# SCH_UWB_AiThinker_BU01_2023-06-05.net
KiCad netlist of a schematic drawn in EasyEDA
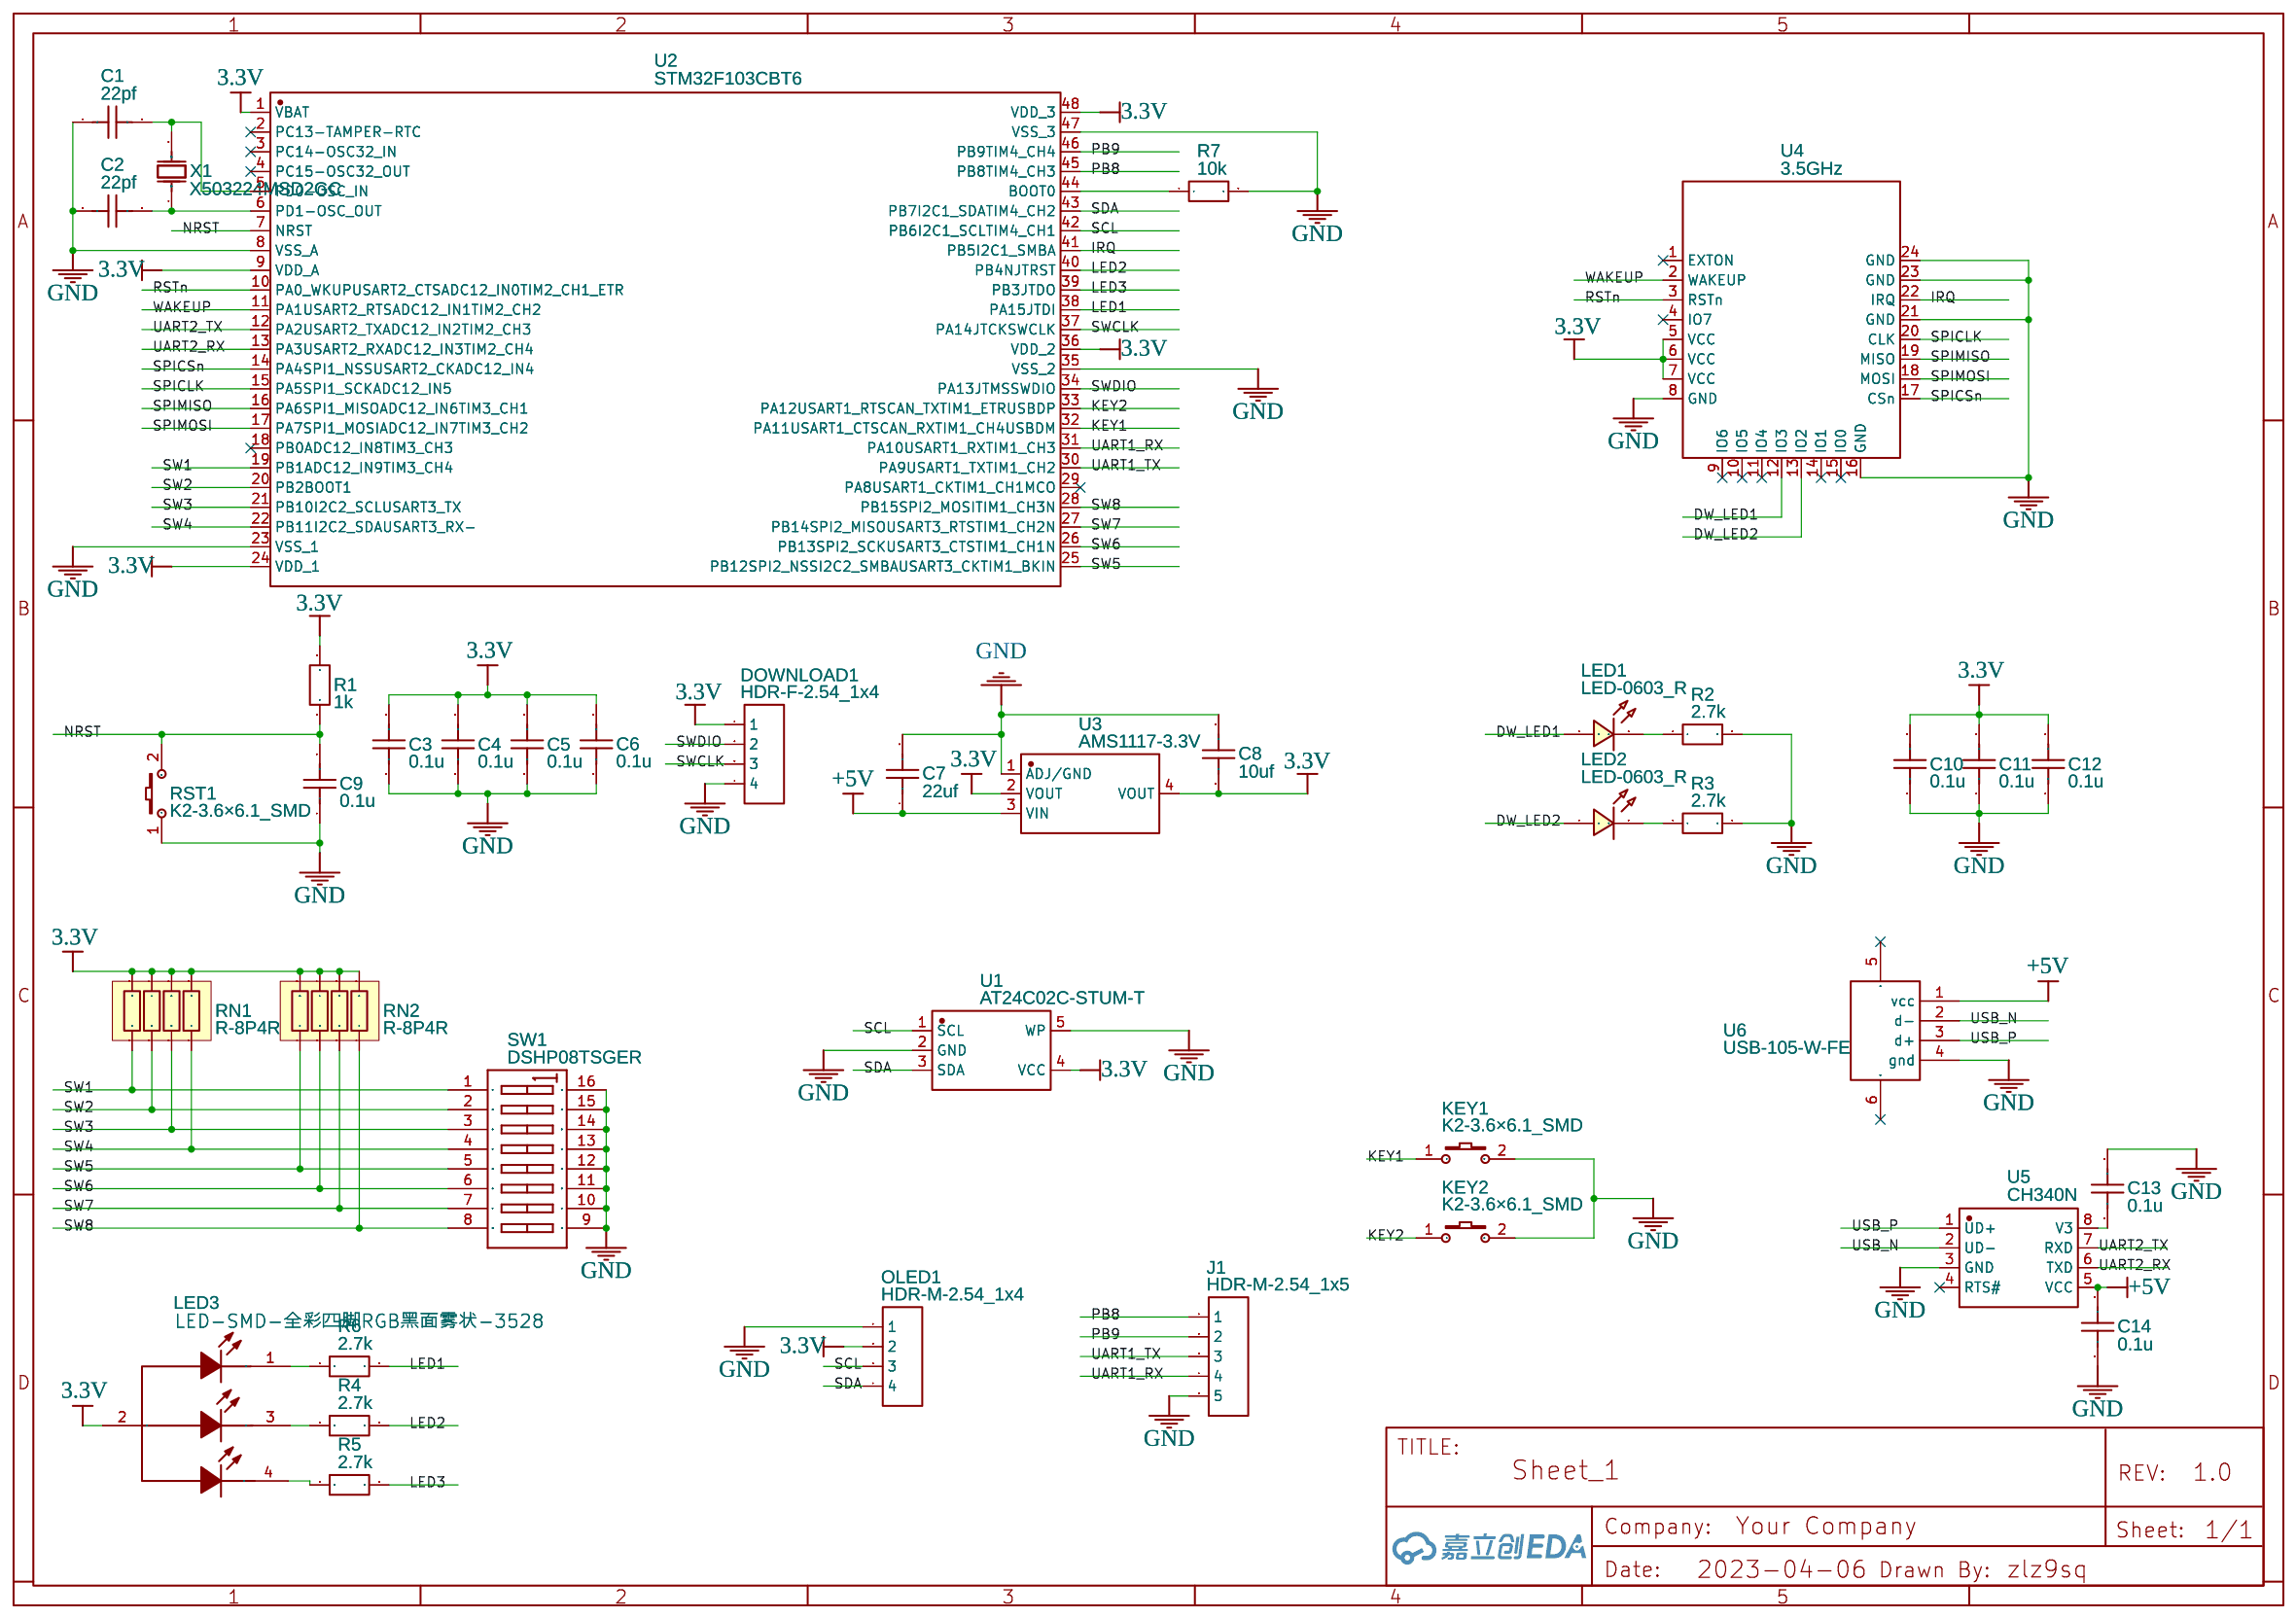
[diagram p0: schematic sheet]

(export (version "E")
  (design (tool "Eeschema 10.0.6"))
  (components
    (comp (ref "C1") (value "22pf") (libsource (lib "") (part "C_0603_US_1")))
    (comp (ref "C2") (value "22pf") (libsource (lib "") (part "C_0603_US_1")))
    (comp (ref "C3") (value "0.1u") (libsource (lib "") (part "C_0603_US")))
    (comp (ref "C4") (value "0.1u") (libsource (lib "") (part "C_0603_US")))
    (comp (ref "C5") (value "0.1u") (libsource (lib "") (part "C_0603_US")))
    (comp (ref "C6") (value "0.1u") (libsource (lib "") (part "C_0603_US")))
    (comp (ref "C7") (value "22uf") (libsource (lib "") (part "C_0805_US_1")))
    (comp (ref "C8") (value "10uf") (libsource (lib "") (part "C_0805_US")))
    (comp (ref "C9") (value "0.1u") (libsource (lib "") (part "C_0603_US")))
    (comp (ref "C10") (value "0.1u") (libsource (lib "") (part "C_0603_US")))
    (comp (ref "C11") (value "0.1u") (libsource (lib "") (part "C_0603_US")))
    (comp (ref "C12") (value "0.1u") (libsource (lib "") (part "C_0603_US")))
    (comp (ref "C13") (value "0.1u") (libsource (lib "") (part "C_0603_US")))
    (comp (ref "C14") (value "0.1u") (libsource (lib "") (part "C_0603_US")))
    (comp (ref "DOWNLOAD1")
      (value "HDR-F-2.54_1x4")
      (fields (field (name "BOM_Supplier Part") "C225501"))
      (libsource (lib "") (part "HDR-F-2.54_1x4"))
    )
    (comp (ref "J1")
      (value "HDR-M-2.54_1x5")
      (fields (field (name "BOM_Supplier Part") "C358687"))
      (libsource (lib "") (part "HDR-M-2.54_1x5"))
    )
    (comp (ref "KEY1")
      (value "K2-3.6×6.1_SMD")
      (fields
        (field (name "BOM_Manufacturer Part") "K2-1107ST-A4SW-06")
        (field (name "BOM_Supplier Part") "C118141")
      )
      (libsource (lib "") (part "K2-3.6×6.1_SMD"))
    )
    (comp (ref "KEY2")
      (value "K2-3.6×6.1_SMD")
      (fields
        (field (name "BOM_Manufacturer Part") "K2-1107ST-A4SW-06")
        (field (name "BOM_Supplier Part") "C118141")
      )
      (libsource (lib "") (part "K2-3.6×6.1_SMD"))
    )
    (comp (ref "LED1")
      (value "LED-0603_R")
      (fields
        (field (name "BOM_Manufacturer Part") "19-217/R6C-AL1M2VY/3T")
        (field (name "BOM_Supplier Part") "C72044")
      )
      (libsource (lib "") (part "LED-0603_R"))
    )
    (comp (ref "LED2")
      (value "LED-0603_R")
      (fields
        (field (name "BOM_Manufacturer Part") "19-217/R6C-AL1M2VY/3T")
        (field (name "BOM_Supplier Part") "C72044")
      )
      (libsource (lib "") (part "LED-0603_R"))
    )
    (comp (ref "LED3")
      (value "LED-SMD-全彩四脚RGB黑面雾状-3528")
      (fields (field (name "BOM_Supplier Part") "C9900014091"))
      (libsource (lib "") (part "LED-SMD-全彩四脚RGB黑面雾状-3528"))
    )
    (comp (ref "OLED1")
      (value "HDR-M-2.54_1x4")
      (fields (field (name "BOM_Supplier Part") "C124378"))
      (libsource (lib "") (part "HDR-M-2.54_1x4"))
    )
    (comp (ref "R1") (value "1k") (libsource (lib "") (part "R_0603_EU")))
    (comp (ref "R2") (value "2.7k") (libsource (lib "") (part "R_0603_EU_1")))
    (comp (ref "R3") (value "2.7k") (libsource (lib "") (part "R_0603_EU_1")))
    (comp (ref "R4") (value "2.7k") (libsource (lib "") (part "R_0603_EU_1")))
    (comp (ref "R5") (value "2.7k") (libsource (lib "") (part "R_0603_EU_1")))
    (comp (ref "R6") (value "2.7k") (libsource (lib "") (part "R_0603_EU_1")))
    (comp (ref "R7") (value "10k") (libsource (lib "") (part "R_0603_EU_1")))
    (comp (ref "RN1") (value "R-8P4R") (libsource (lib "") (part "R-8P4R")))
    (comp (ref "RN2") (value "R-8P4R") (libsource (lib "") (part "R-8P4R")))
    (comp (ref "RST1")
      (value "K2-3.6×6.1_SMD")
      (fields
        (field (name "BOM_Manufacturer Part") "K2-1107ST-A4SW-06")
        (field (name "BOM_Supplier Part") "C118141")
      )
      (libsource (lib "") (part "K2-3.6×6.1_SMD_1"))
    )
    (comp (ref "SW1")
      (value "DSHP08TSGER")
      (fields (field (name "BOM_Supplier Part") "C40738"))
      (libsource (lib "") (part "DSHP08TSGER"))
    )
    (comp (ref "U1")
      (value "AT24C02C-STUM-T")
      (fields (field (name "BOM_Supplier Part") "C94534"))
      (libsource (lib "") (part "AT24C02C-STUM-T"))
    )
    (comp (ref "U2")
      (value "STM32F103CBT6")
      (fields (field (name "BOM_Supplier Part") "C8304"))
      (libsource (lib "") (part "STM32F103CBT6"))
    )
    (comp (ref "U3")
      (value "AMS1117-3.3V")
      (fields (field (name "BOM_Supplier Part") "C2688239"))
      (libsource (lib "") (part "AMS1117-3.3V"))
    )
    (comp (ref "U4")
      (value "3.5GHz")
      (fields (field (name "BOM_Manufacturer Part") "BU01") (field (name "BOM_Supplier Part") "C503604"))
      (libsource (lib "") (part "BU01"))
    )
    (comp (ref "U5")
      (value "CH340N")
      (fields (field (name "BOM_Supplier Part") "C506813"))
      (libsource (lib "") (part "CH340N"))
    )
    (comp (ref "U6")
      (value "USB-105-W-FE")
      (fields (field (name "BOM_Supplier Part") "C2939555"))
      (libsource (lib "") (part "USB-105-W-FE"))
    )
    (comp (ref "X1")
      (value "X503224MSD2GC")
      (fields (field (name "BOM_Supplier Part") "C48304"))
      (libsource (lib "") (part "X503224MSD2GC"))
    )
  )
  (nets
    (net (code "1") (name "+5V") (class "Default")
      (node (ref "C14") (pin "2") (pinfunction "2_2") (pintype "unspecified"))
      (node (ref "C7") (pin "1") (pinfunction "1_1") (pintype "unspecified"))
      (node (ref "U3") (pin "3") (pinfunction "VIN_3") (pintype "unspecified"))
      (node (ref "U5") (pin "5") (pinfunction "VCC_5") (pintype "unspecified"))
      (node (ref "U6") (pin "1") (pinfunction "vcc_1") (pintype "input"))
    )
    (net (code "2") (name "/DW_LED1") (class "Default")
      (node (ref "LED1") (pin "1") (pinfunction "1_1") (pintype "unspecified"))
      (node (ref "U4") (pin "12") (pinfunction "IO3_12") (pintype "unspecified"))
    )
    (net (code "3") (name "/DW_LED2") (class "Default")
      (node (ref "LED2") (pin "1") (pinfunction "1_1") (pintype "unspecified"))
      (node (ref "U4") (pin "13") (pinfunction "IO2_13") (pintype "unspecified"))
    )
    (net (code "4") (name "/IRQ") (class "Default")
      (node (ref "U2") (pin "41") (pinfunction "PB5I2C1_SMBA_41") (pintype "unspecified"))
      (node (ref "U4") (pin "22") (pinfunction "IRQ_22") (pintype "unspecified"))
    )
    (net (code "5") (name "/KEY1") (class "Default")
      (node (ref "KEY1") (pin "1") (pinfunction "1_1") (pintype "unspecified"))
      (node (ref "U2") (pin "32") (pinfunction "PA11USART1_CTSCAN_RXTIM1_CH4USBDM_32") (pintype "unspecified"))
    )
    (net (code "6") (name "/KEY2") (class "Default")
      (node (ref "KEY2") (pin "1") (pinfunction "1_1") (pintype "unspecified"))
      (node (ref "U2") (pin "33") (pinfunction "PA12USART1_RTSCAN_TXTIM1_ETRUSBDP_33") (pintype "unspecified"))
    )
    (net (code "7") (name "/LED1") (class "Default")
      (node (ref "R6") (pin "2") (pinfunction "2_2") (pintype "unspecified"))
      (node (ref "U2") (pin "38") (pinfunction "PA15JTDI_38") (pintype "unspecified"))
    )
    (net (code "8") (name "/LED2") (class "Default")
      (node (ref "R4") (pin "2") (pinfunction "2_2") (pintype "unspecified"))
      (node (ref "U2") (pin "40") (pinfunction "PB4NJTRST_40") (pintype "unspecified"))
    )
    (net (code "9") (name "/LED3") (class "Default")
      (node (ref "R5") (pin "2") (pinfunction "2_2") (pintype "unspecified"))
      (node (ref "U2") (pin "39") (pinfunction "PB3JTDO_39") (pintype "unspecified"))
    )
    (net (code "10") (name "/NRST") (class "Default")
      (node (ref "C9") (pin "2") (pinfunction "2_2") (pintype "unspecified"))
      (node (ref "R1") (pin "1") (pinfunction "1_1") (pintype "unspecified"))
      (node (ref "RST1") (pin "2") (pinfunction "2_2") (pintype "unspecified"))
      (node (ref "U2") (pin "7") (pinfunction "NRST_7") (pintype "unspecified"))
    )
    (net (code "11") (name "/PB8") (class "Default")
      (node (ref "J1") (pin "1") (pinfunction "1_1") (pintype "unspecified"))
      (node (ref "U2") (pin "45") (pinfunction "PB8TIM4_CH3_45") (pintype "unspecified"))
    )
    (net (code "12") (name "/PB9") (class "Default")
      (node (ref "J1") (pin "2") (pinfunction "2_2") (pintype "unspecified"))
      (node (ref "U2") (pin "46") (pinfunction "PB9TIM4_CH4_46") (pintype "unspecified"))
    )
    (net (code "13") (name "/RSTn") (class "Default")
      (node (ref "U2") (pin "10") (pinfunction "PA0_WKUPUSART2_CTSADC12_IN0TIM2_CH1_ETR_10") (pintype "unspecified"))
      (node (ref "U4") (pin "3") (pinfunction "RSTn_3") (pintype "unspecified"))
    )
    (net (code "14") (name "/SCL") (class "Default")
      (node (ref "OLED1") (pin "3") (pinfunction "3_3") (pintype "unspecified"))
      (node (ref "U1") (pin "1") (pinfunction "SCL_1") (pintype "unspecified"))
      (node (ref "U2") (pin "42") (pinfunction "PB6I2C1_SCLTIM4_CH1_42") (pintype "unspecified"))
    )
    (net (code "15") (name "/SDA") (class "Default")
      (node (ref "OLED1") (pin "4") (pinfunction "4_4") (pintype "unspecified"))
      (node (ref "U1") (pin "3") (pinfunction "SDA_3") (pintype "unspecified"))
      (node (ref "U2") (pin "43") (pinfunction "PB7I2C1_SDATIM4_CH2_43") (pintype "unspecified"))
    )
    (net (code "16") (name "/SPICLK") (class "Default")
      (node (ref "U2") (pin "15") (pinfunction "PA5SPI1_SCKADC12_IN5_15") (pintype "unspecified"))
      (node (ref "U4") (pin "20") (pinfunction "CLK_20") (pintype "unspecified"))
    )
    (net (code "17") (name "/SPICSn") (class "Default")
      (node (ref "U2") (pin "14") (pinfunction "PA4SPI1_NSSUSART2_CKADC12_IN4_14") (pintype "unspecified"))
      (node (ref "U4") (pin "17") (pinfunction "CSn_17") (pintype "unspecified"))
    )
    (net (code "18") (name "/SPIMISO") (class "Default")
      (node (ref "U2") (pin "16") (pinfunction "PA6SPI1_MISOADC12_IN6TIM3_CH1_16") (pintype "unspecified"))
      (node (ref "U4") (pin "19") (pinfunction "MISO_19") (pintype "unspecified"))
    )
    (net (code "19") (name "/SPIMOSI") (class "Default")
      (node (ref "U2") (pin "17") (pinfunction "PA7SPI1_MOSIADC12_IN7TIM3_CH2_17") (pintype "unspecified"))
      (node (ref "U4") (pin "18") (pinfunction "MOSI_18") (pintype "unspecified"))
    )
    (net (code "20") (name "/SW1") (class "Default")
      (node (ref "RN1") (pin "1") (pinfunction "1_1") (pintype "unspecified"))
      (node (ref "SW1") (pin "1") (pinfunction "A1_1") (pintype "unspecified"))
      (node (ref "U2") (pin "19") (pinfunction "PB1ADC12_IN9TIM3_CH4_19") (pintype "unspecified"))
    )
    (net (code "21") (name "/SW2") (class "Default")
      (node (ref "RN1") (pin "2") (pinfunction "2_2") (pintype "unspecified"))
      (node (ref "SW1") (pin "2") (pinfunction "A2_2") (pintype "unspecified"))
      (node (ref "U2") (pin "20") (pinfunction "PB2BOOT1_20") (pintype "unspecified"))
    )
    (net (code "22") (name "/SW3") (class "Default")
      (node (ref "RN1") (pin "3") (pinfunction "3_3") (pintype "unspecified"))
      (node (ref "SW1") (pin "3") (pinfunction "A3_3") (pintype "unspecified"))
      (node (ref "U2") (pin "21") (pinfunction "PB10I2C2_SCLUSART3_TX_21") (pintype "unspecified"))
    )
    (net (code "23") (name "/SW4") (class "Default")
      (node (ref "RN1") (pin "4") (pinfunction "4_4") (pintype "unspecified"))
      (node (ref "SW1") (pin "4") (pinfunction "A4_4") (pintype "unspecified"))
      (node (ref "U2") (pin "22") (pinfunction "PB11I2C2_SDAUSART3_RX-_22") (pintype "unspecified"))
    )
    (net (code "24") (name "/SW5") (class "Default")
      (node (ref "RN2") (pin "1") (pinfunction "1_1") (pintype "unspecified"))
      (node (ref "SW1") (pin "5") (pinfunction "A5_5") (pintype "unspecified"))
      (node (ref "U2") (pin "25") (pinfunction "PB12SPI2_NSSI2C2_SMBAUSART3_CKTIM1_BKIN_25") (pintype "unspecified"))
    )
    (net (code "25") (name "/SW6") (class "Default")
      (node (ref "RN2") (pin "2") (pinfunction "2_2") (pintype "unspecified"))
      (node (ref "SW1") (pin "6") (pinfunction "A6_6") (pintype "unspecified"))
      (node (ref "U2") (pin "26") (pinfunction "PB13SPI2_SCKUSART3_CTSTIM1_CH1N_26") (pintype "unspecified"))
    )
    (net (code "26") (name "/SW7") (class "Default")
      (node (ref "RN2") (pin "3") (pinfunction "3_3") (pintype "unspecified"))
      (node (ref "SW1") (pin "7") (pinfunction "A7_7") (pintype "unspecified"))
      (node (ref "U2") (pin "27") (pinfunction "PB14SPI2_MISOUSART3_RTSTIM1_CH2N_27") (pintype "unspecified"))
    )
    (net (code "27") (name "/SW8") (class "Default")
      (node (ref "RN2") (pin "4") (pinfunction "4_4") (pintype "unspecified"))
      (node (ref "SW1") (pin "8") (pinfunction "A8_8") (pintype "unspecified"))
      (node (ref "U2") (pin "28") (pinfunction "PB15SPI2_MOSITIM1_CH3N_28") (pintype "unspecified"))
    )
    (net (code "28") (name "/SWCLK") (class "Default")
      (node (ref "DOWNLOAD1") (pin "3") (pinfunction "3_3") (pintype "unspecified"))
      (node (ref "U2") (pin "37") (pinfunction "PA14JTCKSWCLK_37") (pintype "unspecified"))
    )
    (net (code "29") (name "/SWDIO") (class "Default")
      (node (ref "DOWNLOAD1") (pin "2") (pinfunction "2_2") (pintype "unspecified"))
      (node (ref "U2") (pin "34") (pinfunction "PA13JTMSSWDIO_34") (pintype "unspecified"))
    )
    (net (code "30") (name "/UART1_RX") (class "Default")
      (node (ref "J1") (pin "4") (pinfunction "4_4") (pintype "unspecified"))
      (node (ref "U2") (pin "31") (pinfunction "PA10USART1_RXTIM1_CH3_31") (pintype "unspecified"))
    )
    (net (code "31") (name "/UART1_TX") (class "Default")
      (node (ref "J1") (pin "3") (pinfunction "3_3") (pintype "unspecified"))
      (node (ref "U2") (pin "30") (pinfunction "PA9USART1_TXTIM1_CH2_30") (pintype "unspecified"))
    )
    (net (code "32") (name "/UART2_RX") (class "Default")
      (node (ref "U2") (pin "13") (pinfunction "PA3USART2_RXADC12_IN3TIM2_CH4_13") (pintype "unspecified"))
      (node (ref "U5") (pin "6") (pinfunction "TXD_6") (pintype "unspecified"))
    )
    (net (code "33") (name "/UART2_TX") (class "Default")
      (node (ref "U2") (pin "12") (pinfunction "PA2USART2_TXADC12_IN2TIM2_CH3_12") (pintype "unspecified"))
      (node (ref "U5") (pin "7") (pinfunction "RXD_7") (pintype "unspecified"))
    )
    (net (code "34") (name "/USB_N") (class "Default")
      (node (ref "U5") (pin "2") (pinfunction "UD-_2") (pintype "unspecified"))
      (node (ref "U6") (pin "2") (pinfunction "d-_2") (pintype "input"))
    )
    (net (code "35") (name "/USB_P") (class "Default")
      (node (ref "U5") (pin "1") (pinfunction "UD+_1") (pintype "unspecified"))
      (node (ref "U6") (pin "3") (pinfunction "d+_3") (pintype "input"))
    )
    (net (code "36") (name "/WAKEUP") (class "Default")
      (node (ref "U2") (pin "11") (pinfunction "PA1USART2_RTSADC12_IN1TIM2_CH2_11") (pintype "unspecified"))
      (node (ref "U4") (pin "2") (pinfunction "WAKEUP_2") (pintype "unspecified"))
    )
    (net (code "37") (name "3.3V") (class "Default")
      (node (ref "C10") (pin "2") (pinfunction "2_2") (pintype "unspecified"))
      (node (ref "C11") (pin "2") (pinfunction "2_2") (pintype "unspecified"))
      (node (ref "C12") (pin "2") (pinfunction "2_2") (pintype "unspecified"))
      (node (ref "C3") (pin "2") (pinfunction "2_2") (pintype "unspecified"))
      (node (ref "C4") (pin "2") (pinfunction "2_2") (pintype "unspecified"))
      (node (ref "C5") (pin "2") (pinfunction "2_2") (pintype "unspecified"))
      (node (ref "C6") (pin "2") (pinfunction "2_2") (pintype "unspecified"))
      (node (ref "C8") (pin "2") (pinfunction "2_2") (pintype "unspecified"))
      (node (ref "DOWNLOAD1") (pin "1") (pinfunction "1_1") (pintype "unspecified"))
      (node (ref "LED3") (pin "2") (pinfunction "2_2") (pintype "unspecified"))
      (node (ref "OLED1") (pin "2") (pinfunction "2_2") (pintype "unspecified"))
      (node (ref "R1") (pin "2") (pinfunction "2_2") (pintype "unspecified"))
      (node (ref "RN1") (pin "5") (pinfunction "5_5") (pintype "unspecified"))
      (node (ref "RN1") (pin "6") (pinfunction "6_6") (pintype "unspecified"))
      (node (ref "RN1") (pin "7") (pinfunction "7_7") (pintype "unspecified"))
      (node (ref "RN1") (pin "8") (pinfunction "8_8") (pintype "unspecified"))
      (node (ref "RN2") (pin "5") (pinfunction "5_5") (pintype "unspecified"))
      (node (ref "RN2") (pin "6") (pinfunction "6_6") (pintype "unspecified"))
      (node (ref "RN2") (pin "7") (pinfunction "7_7") (pintype "unspecified"))
      (node (ref "RN2") (pin "8") (pinfunction "8_8") (pintype "unspecified"))
      (node (ref "U1") (pin "4") (pinfunction "VCC_4") (pintype "unspecified"))
      (node (ref "U2") (pin "1") (pinfunction "VBAT_1") (pintype "unspecified"))
      (node (ref "U2") (pin "24") (pinfunction "VDD_1_24") (pintype "unspecified"))
      (node (ref "U2") (pin "36") (pinfunction "VDD_2_36") (pintype "unspecified"))
      (node (ref "U2") (pin "48") (pinfunction "VDD_3_48") (pintype "unspecified"))
      (node (ref "U2") (pin "9") (pinfunction "VDD_A_9") (pintype "unspecified"))
      (node (ref "U3") (pin "2") (pinfunction "VOUT_2") (pintype "unspecified"))
      (node (ref "U3") (pin "4") (pinfunction "VOUT_4") (pintype "unspecified"))
      (node (ref "U4") (pin "5") (pinfunction "VCC_5") (pintype "unspecified"))
      (node (ref "U4") (pin "6") (pinfunction "VCC_6") (pintype "unspecified"))
      (node (ref "U4") (pin "7") (pinfunction "VCC_7") (pintype "unspecified"))
    )
    (net (code "38") (name "GND") (class "Default")
      (node (ref "C1") (pin "1") (pinfunction "1_1") (pintype "unspecified"))
      (node (ref "C10") (pin "1") (pinfunction "1_1") (pintype "unspecified"))
      (node (ref "C11") (pin "1") (pinfunction "1_1") (pintype "unspecified"))
      (node (ref "C12") (pin "1") (pinfunction "1_1") (pintype "unspecified"))
      (node (ref "C13") (pin "2") (pinfunction "2_2") (pintype "unspecified"))
      (node (ref "C14") (pin "1") (pinfunction "1_1") (pintype "unspecified"))
      (node (ref "C2") (pin "1") (pinfunction "1_1") (pintype "unspecified"))
      (node (ref "C3") (pin "1") (pinfunction "1_1") (pintype "unspecified"))
      (node (ref "C4") (pin "1") (pinfunction "1_1") (pintype "unspecified"))
      (node (ref "C5") (pin "1") (pinfunction "1_1") (pintype "unspecified"))
      (node (ref "C6") (pin "1") (pinfunction "1_1") (pintype "unspecified"))
      (node (ref "C7") (pin "2") (pinfunction "2_2") (pintype "unspecified"))
      (node (ref "C8") (pin "1") (pinfunction "1_1") (pintype "unspecified"))
      (node (ref "C9") (pin "1") (pinfunction "1_1") (pintype "unspecified"))
      (node (ref "DOWNLOAD1") (pin "4") (pinfunction "4_4") (pintype "unspecified"))
      (node (ref "J1") (pin "5") (pinfunction "5_5") (pintype "unspecified"))
      (node (ref "KEY1") (pin "2") (pinfunction "2_2") (pintype "unspecified"))
      (node (ref "KEY2") (pin "2") (pinfunction "2_2") (pintype "unspecified"))
      (node (ref "OLED1") (pin "1") (pinfunction "1_1") (pintype "unspecified"))
      (node (ref "R2") (pin "2") (pinfunction "2_2") (pintype "unspecified"))
      (node (ref "R3") (pin "2") (pinfunction "2_2") (pintype "unspecified"))
      (node (ref "R7") (pin "2") (pinfunction "2_2") (pintype "unspecified"))
      (node (ref "RST1") (pin "1") (pinfunction "1_1") (pintype "unspecified"))
      (node (ref "SW1") (pin "10") (pinfunction "B7_10") (pintype "unspecified"))
      (node (ref "SW1") (pin "11") (pinfunction "B6_11") (pintype "unspecified"))
      (node (ref "SW1") (pin "12") (pinfunction "B5_12") (pintype "unspecified"))
      (node (ref "SW1") (pin "13") (pinfunction "B4_13") (pintype "unspecified"))
      (node (ref "SW1") (pin "14") (pinfunction "B3_14") (pintype "unspecified"))
      (node (ref "SW1") (pin "15") (pinfunction "B2_15") (pintype "unspecified"))
      (node (ref "SW1") (pin "16") (pinfunction "B1_16") (pintype "unspecified"))
      (node (ref "SW1") (pin "9") (pinfunction "B8_9") (pintype "unspecified"))
      (node (ref "U1") (pin "2") (pinfunction "GND_2") (pintype "unspecified"))
      (node (ref "U1") (pin "5") (pinfunction "WP_5") (pintype "unspecified"))
      (node (ref "U2") (pin "23") (pinfunction "VSS_1_23") (pintype "unspecified"))
      (node (ref "U2") (pin "35") (pinfunction "VSS_2_35") (pintype "unspecified"))
      (node (ref "U2") (pin "47") (pinfunction "VSS_3_47") (pintype "unspecified"))
      (node (ref "U2") (pin "8") (pinfunction "VSS_A_8") (pintype "unspecified"))
      (node (ref "U3") (pin "1") (pinfunction "ADJ/GND_1") (pintype "unspecified"))
      (node (ref "U4") (pin "16") (pinfunction "GND_16") (pintype "unspecified"))
      (node (ref "U4") (pin "21") (pinfunction "GND_21") (pintype "unspecified"))
      (node (ref "U4") (pin "23") (pinfunction "GND_23") (pintype "unspecified"))
      (node (ref "U4") (pin "24") (pinfunction "GND_24") (pintype "unspecified"))
      (node (ref "U4") (pin "8") (pinfunction "GND_8") (pintype "unspecified"))
      (node (ref "U5") (pin "3") (pinfunction "GND_3") (pintype "unspecified"))
      (node (ref "U6") (pin "4") (pinfunction "gnd_4") (pintype "input"))
    )
    (net (code "39") (name "Net-(LED1-Pad2)") (class "Default")
      (node (ref "LED1") (pin "2") (pinfunction "2_2") (pintype "unspecified"))
      (node (ref "R2") (pin "1") (pinfunction "1_1") (pintype "unspecified"))
    )
    (net (code "40") (name "Net-(LED2-Pad2)") (class "Default")
      (node (ref "LED2") (pin "2") (pinfunction "2_2") (pintype "unspecified"))
      (node (ref "R3") (pin "1") (pinfunction "1_1") (pintype "unspecified"))
    )
    (net (code "41") (name "Net-(LED3-B)") (class "Default")
      (node (ref "LED3") (pin "3") (pinfunction "B_3") (pintype "unspecified"))
      (node (ref "R4") (pin "1") (pinfunction "1_1") (pintype "unspecified"))
    )
    (net (code "42") (name "Net-(LED3-G)") (class "Default")
      (node (ref "LED3") (pin "4") (pinfunction "G_4") (pintype "unspecified"))
      (node (ref "R5") (pin "1") (pinfunction "1_1") (pintype "unspecified"))
    )
    (net (code "43") (name "Net-(LED3-R)") (class "Default")
      (node (ref "LED3") (pin "1") (pinfunction "R_1") (pintype "unspecified"))
      (node (ref "R6") (pin "1") (pinfunction "1_1") (pintype "unspecified"))
    )
    (net (code "44") (name "Net-(U2-BOOT0)") (class "Default")
      (node (ref "R7") (pin "1") (pinfunction "1_1") (pintype "unspecified"))
      (node (ref "U2") (pin "44") (pinfunction "BOOT0_44") (pintype "unspecified"))
    )
    (net (code "45") (name "Net-(U2-PD0-OSC_IN)") (class "Default")
      (node (ref "C1") (pin "2") (pinfunction "2_2") (pintype "unspecified"))
      (node (ref "U2") (pin "5") (pinfunction "PD0-OSC_IN_5") (pintype "unspecified"))
      (node (ref "X1") (pin "2") (pinfunction "OSC2_2") (pintype "input"))
    )
    (net (code "46") (name "Net-(U2-PD1-OSC_OUT)") (class "Default")
      (node (ref "C2") (pin "2") (pinfunction "2_2") (pintype "unspecified"))
      (node (ref "U2") (pin "6") (pinfunction "PD1-OSC_OUT_6") (pintype "unspecified"))
      (node (ref "X1") (pin "1") (pinfunction "OSC1_1") (pintype "input"))
    )
    (net (code "47") (name "Net-(U5-V3)") (class "Default")
      (node (ref "C13") (pin "1") (pinfunction "1_1") (pintype "unspecified"))
      (node (ref "U5") (pin "8") (pinfunction "V3_8") (pintype "unspecified"))
    )
    (net (code "48") (name "unconnected-(U2-PA8USART1_CKTIM1_CH1MCO-Pad29)") (class "Default")
      (node (ref "U2") (pin "29") (pinfunction "PA8USART1_CKTIM1_CH1MCO_29") (pintype "unspecified+no_connect"))
    )
    (net (code "49") (name "unconnected-(U2-PB0ADC12_IN8TIM3_CH3-Pad18)") (class "Default")
      (node (ref "U2") (pin "18") (pinfunction "PB0ADC12_IN8TIM3_CH3_18") (pintype "unspecified+no_connect"))
    )
    (net (code "50") (name "unconnected-(U2-PC13-TAMPER-RTC-Pad2)") (class "Default")
      (node (ref "U2") (pin "2") (pinfunction "PC13-TAMPER-RTC_2") (pintype "unspecified+no_connect"))
    )
    (net (code "51") (name "unconnected-(U2-PC14-OSC32_IN-Pad3)") (class "Default")
      (node (ref "U2") (pin "3") (pinfunction "PC14-OSC32_IN_3") (pintype "unspecified+no_connect"))
    )
    (net (code "52") (name "unconnected-(U2-PC15-OSC32_OUT-Pad4)") (class "Default")
      (node (ref "U2") (pin "4") (pinfunction "PC15-OSC32_OUT_4") (pintype "unspecified+no_connect"))
    )
    (net (code "53") (name "unconnected-(U4-EXTON-Pad1)") (class "Default")
      (node (ref "U4") (pin "1") (pinfunction "EXTON_1") (pintype "unspecified+no_connect"))
    )
    (net (code "54") (name "unconnected-(U4-IO0-Pad15)") (class "Default")
      (node (ref "U4") (pin "15") (pinfunction "IO0_15") (pintype "unspecified+no_connect"))
    )
    (net (code "55") (name "unconnected-(U4-IO1-Pad14)") (class "Default")
      (node (ref "U4") (pin "14") (pinfunction "IO1_14") (pintype "unspecified+no_connect"))
    )
    (net (code "56") (name "unconnected-(U4-IO4-Pad11)") (class "Default")
      (node (ref "U4") (pin "11") (pinfunction "IO4_11") (pintype "unspecified+no_connect"))
    )
    (net (code "57") (name "unconnected-(U4-IO5-Pad10)") (class "Default")
      (node (ref "U4") (pin "10") (pinfunction "IO5_10") (pintype "unspecified+no_connect"))
    )
    (net (code "58") (name "unconnected-(U4-IO6-Pad9)") (class "Default")
      (node (ref "U4") (pin "9") (pinfunction "IO6_9") (pintype "unspecified+no_connect"))
    )
    (net (code "59") (name "unconnected-(U4-IO7-Pad4)") (class "Default")
      (node (ref "U4") (pin "4") (pinfunction "IO7_4") (pintype "unspecified+no_connect"))
    )
    (net (code "60") (name "unconnected-(U5-RTS#-Pad4)") (class "Default")
      (node (ref "U5") (pin "4") (pinfunction "RTS#_4") (pintype "unspecified+no_connect"))
    )
    (net (code "61") (name "unconnected-(U6-Pad5)") (class "Default")
      (node (ref "U6") (pin "5") (pinfunction "5_5") (pintype "unspecified+no_connect"))
    )
    (net (code "62") (name "unconnected-(U6-Pad6)") (class "Default")
      (node (ref "U6") (pin "6") (pinfunction "6_6") (pintype "unspecified+no_connect"))
    )
  )
)
